# Power_supply_UCM.net
KiCad netlist of a schematic drawn in Altium Designer
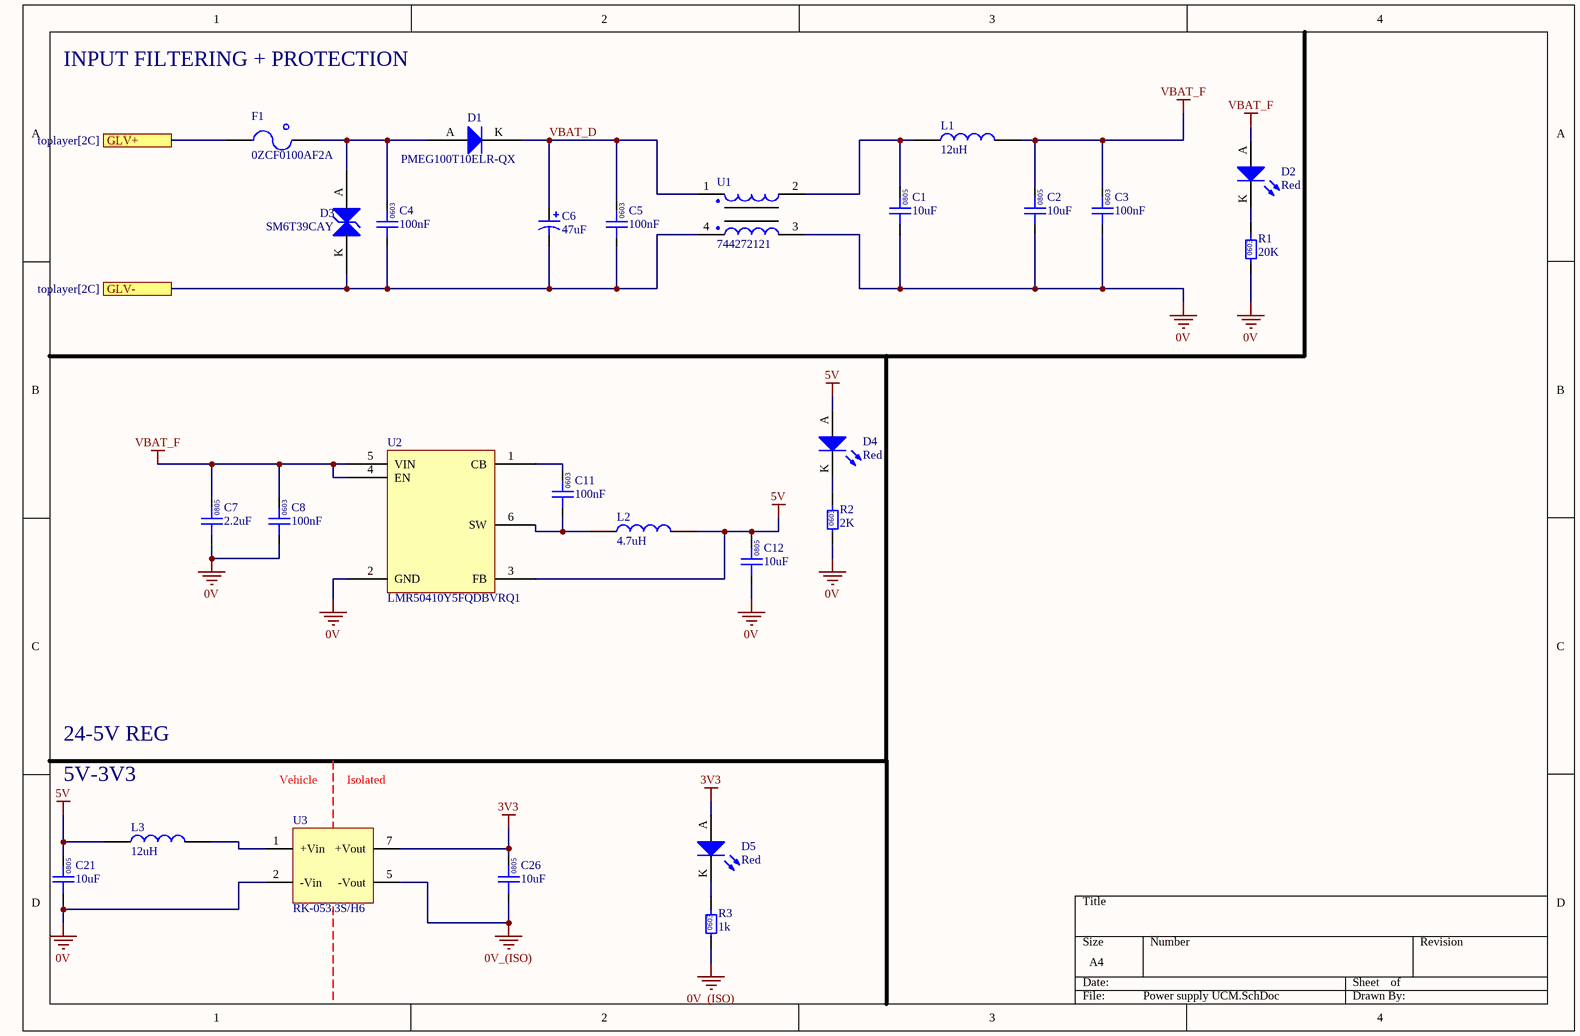
[diagram p0: Power supply UCM.SchDoc]

(export (version "E")
  (design (tool "Eeschema 10.0.6"))
  (components
    (comp (ref "C1")
      (value "10uF")
      (footprint "0805")
      (fields
        (field (name "PART NUMBER") "GRM21BR6YA106KE43L")
        (field (name "MANUFACTURER") "muRata")
        (field (name "TOLERANCE") "10%")
      )
      (libsource (lib "ts_standard_library") (part "Capacitor 0805"))
    )
    (comp (ref "C2")
      (value "10uF")
      (footprint "0805")
      (fields
        (field (name "PART NUMBER") "GRM21BR6YA106KE43L")
        (field (name "MANUFACTURER") "muRata")
        (field (name "TOLERANCE") "10%")
      )
      (libsource (lib "ts_standard_library") (part "Capacitor 0805"))
    )
    (comp (ref "C3")
      (value "100nF")
      (footprint "0603")
      (fields
        (field (name "PART NUMBER") "GCM188L81H104KA57D")
        (field (name "MANUFACTURER") "muRata")
        (field (name "TOLERANCE") "±10%")
      )
      (libsource (lib "ts_standard_library") (part "Capacitor 0603"))
    )
    (comp (ref "C4")
      (value "100nF")
      (footprint "0603")
      (fields
        (field (name "PART NUMBER") "GCM188L81H104KA57D")
        (field (name "MANUFACTURER") "muRata")
        (field (name "TOLERANCE") "±10%")
      )
      (libsource (lib "ts_standard_library") (part "Capacitor 0603"))
    )
    (comp (ref "C5")
      (value "100nF")
      (footprint "0603")
      (fields
        (field (name "PART NUMBER") "GCM188L81H104KA57D")
        (field (name "MANUFACTURER") "muRata")
        (field (name "TOLERANCE") "±10%")
      )
      (libsource (lib "ts_standard_library") (part "Capacitor 0603"))
    )
    (comp (ref "C6")
      (value "47uF")
      (footprint "CHEMI-CON ELCO")
      (fields (field (name "PART NUMBER") "HHXA350ARA470MF61G"))
      (libsource (lib "ts_standard_library") (part "Capacitor (Polarised)"))
    )
    (comp (ref "C7")
      (value "2.2uF")
      (footprint "0805")
      (fields
        (field (name "PART NUMBER") "GRM21BR61A226ME51L")
        (field (name "MANUFACTURER") "muRata")
        (field (name "TOLERANCE") "20%")
      )
      (libsource (lib "ts_standard_library") (part "Capacitor 0805"))
    )
    (comp (ref "C8")
      (value "100nF")
      (footprint "0603")
      (fields
        (field (name "PART NUMBER") "GCM188L81H104KA57D")
        (field (name "MANUFACTURER") "muRata")
        (field (name "TOLERANCE") "±10%")
      )
      (libsource (lib "ts_standard_library") (part "Capacitor 0603"))
    )
    (comp (ref "C11")
      (value "100nF")
      (footprint "0603")
      (fields
        (field (name "PART NUMBER") "GCM188L81H104KA57D")
        (field (name "MANUFACTURER") "muRata")
        (field (name "TOLERANCE") "±10%")
      )
      (libsource (lib "ts_standard_library") (part "Capacitor 0603"))
    )
    (comp (ref "C12")
      (value "10uF")
      (footprint "0805")
      (fields
        (field (name "PART NUMBER") "GRM21BR6YA106KE43L")
        (field (name "MANUFACTURER") "muRata")
        (field (name "TOLERANCE") "10%")
      )
      (libsource (lib "ts_standard_library") (part "Capacitor 0805"))
    )
    (comp (ref "C21")
      (value "10uF")
      (footprint "0805")
      (fields
        (field (name "PART NUMBER") "GRM21BR6YA106KE43L")
        (field (name "MANUFACTURER") "muRata")
        (field (name "TOLERANCE") "10%")
      )
      (libsource (lib "ts_standard_library") (part "Capacitor 0805"))
    )
    (comp (ref "C26")
      (value "10uF")
      (footprint "0805")
      (fields
        (field (name "PART NUMBER") "GRM21BR6YA106KE43L")
        (field (name "MANUFACTURER") "muRata")
        (field (name "TOLERANCE") "10%")
      )
      (libsource (lib "ts_standard_library") (part "Capacitor 0805"))
    )
    (comp (ref "D1")
      (value "PMEG100T10ELR-QX")
      (footprint "SODFL350X110-2N")
      (description "Diode 100 V 1A Surface Mount SOD-123W")
      (libsource (lib "Team Swinburne") (part "PMEG100T10ELR-QX"))
    )
    (comp (ref "D2")
      (value "Red")
      (footprint "0805 LED")
      (description "Red LED Indication - Discrete 1.75V 0805 (2012 Metric)")
      (fields (field (name "PART NUMBER") "SML-210LTT86") (field (name "MANUFACTURER") "ROHM Semiconductor"))
      (libsource (lib "ts_standard_library") (part "LED"))
    )
    (comp (ref "D3")
      (value "SM6T39CAY")
      (footprint "SM6T39CAY-Footprint-1")
      (description "TVS Diode Single Bi-Dir 33.3V 600W Automotive 2-Pin SMB T/R / TVS DIODE 33.3VWM 69.7VC SMB")
      (libsource (lib "Team Swinburne") (part "SM6T39CAY-Symbol"))
    )
    (comp (ref "D4")
      (value "Red")
      (footprint "0805 LED")
      (description "Red LED Indication - Discrete 1.75V 0805 (2012 Metric)")
      (fields (field (name "PART NUMBER") "SML-210LTT86") (field (name "MANUFACTURER") "ROHM Semiconductor"))
      (libsource (lib "ts_standard_library") (part "LED"))
    )
    (comp (ref "D5")
      (value "Red")
      (footprint "0805 LED")
      (description "Red LED Indication - Discrete 1.75V 0805 (2012 Metric)")
      (fields (field (name "PART NUMBER") "SML-210LTT86") (field (name "MANUFACTURER") "ROHM Semiconductor"))
      (libsource (lib "ts_standard_library") (part "LED"))
    )
    (comp (ref "F1")
      (value "0ZCF0100AF2A")
      (footprint "2920")
      (description "PTC RESET FUSE 60V 1A 292")
      (fields
        (field (name "MANUFACTURER") "Littelfuse Inc.")
        (field (name "DIGIKEY PART NUMBER") "507-2070-1-ND")
      )
      (libsource (lib "ts_standard_library") (part "PTC Fuse"))
    )
    (comp (ref "L1")
      (value "12uH")
      (footprint "1812")
      (fields
        (field (name "PART NUMBER") "RLS-126")
        (field (name "MANUFACTURER") "Recom")
        (field (name "TOLERANCE") "0.2")
      )
      (libsource (lib "ts_standard_library") (part "Inductor"))
    )
    (comp (ref "L2")
      (value "4.7uH")
      (footprint "SRN3015TA-4R7M")
      (fields
        (field (name "PART NUMBER") "SRN4018-4R7M")
        (field (name "MANUFACTURER") "Bourns")
        (field (name "TOLERANCE") "0.2")
      )
      (libsource (lib "ts_standard_library") (part "Inductor"))
    )
    (comp (ref "L3")
      (value "12uH")
      (footprint "1812")
      (fields
        (field (name "PART NUMBER") "RLS-126")
        (field (name "MANUFACTURER") "Recom")
        (field (name "TOLERANCE") "0.2")
      )
      (libsource (lib "ts_standard_library") (part "Inductor"))
    )
    (comp (ref "R1")
      (value "20K")
      (footprint "0603")
      (fields
        (field (name "PART NUMBER") "RC0603FR-0720KL")
        (field (name "MANUFACTURER") "YAGEO")
        (field (name "TOLERANCE") "0.01")
      )
      (libsource (lib "ts_standard_library") (part "Resistor 0603"))
    )
    (comp (ref "R2")
      (value "2K")
      (footprint "0603")
      (fields
        (field (name "PART NUMBER") "RC0603FR-072KL")
        (field (name "MANUFACTURER") "YAGEO")
        (field (name "TOLERANCE") "0.01")
      )
      (libsource (lib "ts_standard_library") (part "Resistor 0603"))
    )
    (comp (ref "R3")
      (value "1k")
      (footprint "0603")
      (fields
        (field (name "PART NUMBER") "RC0603FR-071KL")
        (field (name "MANUFACTURER") "YAGEO")
        (field (name "TOLERANCE") "0.01")
      )
      (libsource (lib "ts_standard_library") (part "Resistor 0603"))
    )
    (comp (ref "U1")
      (value "744272121")
      (footprint "Wurth 4-PC Pad")
      (fields
        (field (name "MANUFACTURER") "Wurth Electronics Inc")
        (field (name "DIGIKEY PART NUMBER") "732-1489-1-ND")
      )
      (libsource (lib "ts_standard_library") (part "CM Choke"))
    )
    (comp (ref "U2")
      (value "LMR50410Y5FQDBVRQ1")
      (footprint "TI-SOT23-6")
      (description "IC REG BUCK 5V 1A SOT23-6")
      (fields (field (name "PART NUMBER") "LMR50410-Q1") (field (name "MANUFACTURER") "Texas Instruments"))
      (libsource (lib "ts_standard_library") (part "LMR50410Y5FQDBVRQ1"))
    )
    (comp (ref "U3")
      (value "RK-053.3S/H6")
      (footprint "RK-053.3S/H6")
      (description "DC DC CONVERTER 3.3V 1W")
      (fields (field (name "MANUFACTURER") "Recom"))
      (libsource (lib "ts_standard_library") (part "RK-053.3S/H6"))
    )
  )
  (nets
    (net (code "1") (name "/GLV+") (class "Default")
      (node (ref "F1") (pin "1") (pinfunction "1_1") (pintype "passive"))
    )
    (net (code "2") (name "/GLV-") (class "Default")
      (node (ref "C4") (pin "1") (pinfunction "1_1") (pintype "passive"))
      (node (ref "C5") (pin "1") (pinfunction "1_1") (pintype "passive"))
      (node (ref "C6") (pin "1") (pinfunction "1_1") (pintype "passive"))
      (node (ref "D3") (pin "K") (pintype "passive"))
      (node (ref "U1") (pin "4") (pinfunction "4_4") (pintype "passive"))
    )
    (net (code "3") (name "/VBAT_D") (class "Default")
      (node (ref "C5") (pin "2") (pinfunction "2_2") (pintype "passive"))
      (node (ref "C6") (pin "2") (pinfunction "2_2") (pintype "passive"))
      (node (ref "D1") (pin "K") (pintype "passive"))
      (node (ref "U1") (pin "1") (pinfunction "1_1") (pintype "passive"))
    )
    (net (code "4") (name "0V") (class "Default")
      (node (ref "C1") (pin "1") (pinfunction "1_1") (pintype "passive"))
      (node (ref "C12") (pin "1") (pinfunction "1_1") (pintype "passive"))
      (node (ref "C2") (pin "1") (pinfunction "1_1") (pintype "passive"))
      (node (ref "C21") (pin "1") (pinfunction "1_1") (pintype "passive"))
      (node (ref "C3") (pin "1") (pinfunction "1_1") (pintype "passive"))
      (node (ref "C7") (pin "1") (pinfunction "1_1") (pintype "passive"))
      (node (ref "C8") (pin "1") (pinfunction "1_1") (pintype "passive"))
      (node (ref "R1") (pin "1") (pinfunction "1_1") (pintype "passive"))
      (node (ref "R2") (pin "1") (pinfunction "1_1") (pintype "passive"))
      (node (ref "U1") (pin "3") (pinfunction "3_3") (pintype "power_in"))
      (node (ref "U2") (pin "2") (pinfunction "GND_2") (pintype "passive"))
      (node (ref "U3") (pin "2") (pinfunction "-Vin_2") (pintype "power_in"))
    )
    (net (code "5") (name "0V_(ISO)") (class "Default")
      (node (ref "C26") (pin "1") (pinfunction "1_1") (pintype "passive"))
      (node (ref "R3") (pin "1") (pinfunction "1_1") (pintype "passive"))
      (node (ref "U3") (pin "5") (pinfunction "-Vout_5") (pintype "power_in"))
    )
    (net (code "6") (name "3V3") (class "Default")
      (node (ref "C26") (pin "2") (pinfunction "2_2") (pintype "passive"))
      (node (ref "D5") (pin "A") (pinfunction "A_A") (pintype "passive"))
      (node (ref "U3") (pin "7") (pinfunction "+Vout_7") (pintype "power_in"))
    )
    (net (code "7") (name "5V") (class "Default")
      (node (ref "C12") (pin "2") (pinfunction "2_2") (pintype "passive"))
      (node (ref "C21") (pin "2") (pinfunction "2_2") (pintype "passive"))
      (node (ref "D4") (pin "A") (pinfunction "A_A") (pintype "passive"))
      (node (ref "L2") (pin "1") (pinfunction "1_1") (pintype "passive"))
      (node (ref "L3") (pin "2") (pinfunction "2_2") (pintype "passive"))
      (node (ref "U2") (pin "3") (pinfunction "FB_3") (pintype "passive"))
    )
    (net (code "8") (name "Net-(C1-Pad2)") (class "Default")
      (node (ref "C1") (pin "2") (pinfunction "2_2") (pintype "passive"))
      (node (ref "L1") (pin "2") (pinfunction "2_2") (pintype "passive"))
      (node (ref "U1") (pin "2") (pinfunction "2_2") (pintype "passive"))
    )
    (net (code "9") (name "Net-(C4-Pad2)") (class "Default")
      (node (ref "C4") (pin "2") (pinfunction "2_2") (pintype "passive"))
      (node (ref "D1") (pin "A") (pintype "passive"))
      (node (ref "D3") (pin "A") (pintype "passive"))
      (node (ref "F1") (pin "2") (pinfunction "2_2") (pintype "passive"))
    )
    (net (code "10") (name "Net-(D2-PadK)") (class "Default")
      (node (ref "D2") (pin "K") (pinfunction "K_K") (pintype "passive"))
      (node (ref "R1") (pin "2") (pinfunction "2_2") (pintype "passive"))
    )
    (net (code "11") (name "Net-(D4-PadK)") (class "Default")
      (node (ref "D4") (pin "K") (pinfunction "K_K") (pintype "passive"))
      (node (ref "R2") (pin "2") (pinfunction "2_2") (pintype "passive"))
    )
    (net (code "12") (name "Net-(D5-PadK)") (class "Default")
      (node (ref "D5") (pin "K") (pinfunction "K_K") (pintype "passive"))
      (node (ref "R3") (pin "2") (pinfunction "2_2") (pintype "passive"))
    )
    (net (code "13") (name "Net-(U2-CB)") (class "Default")
      (node (ref "C11") (pin "2") (pinfunction "2_2") (pintype "passive"))
      (node (ref "U2") (pin "1") (pinfunction "CB_1") (pintype "passive"))
    )
    (net (code "14") (name "Net-(U2-SW)") (class "Default")
      (node (ref "C11") (pin "1") (pinfunction "1_1") (pintype "passive"))
      (node (ref "L2") (pin "2") (pinfunction "2_2") (pintype "passive"))
      (node (ref "U2") (pin "6") (pinfunction "SW_6") (pintype "passive"))
    )
    (net (code "15") (name "Net-(U3-+Vin)") (class "Default")
      (node (ref "L3") (pin "1") (pinfunction "1_1") (pintype "passive"))
      (node (ref "U3") (pin "1") (pinfunction "+Vin_1") (pintype "power_in"))
    )
    (net (code "16") (name "VBAT_F") (class "Default")
      (node (ref "C2") (pin "2") (pinfunction "2_2") (pintype "passive"))
      (node (ref "C3") (pin "2") (pinfunction "2_2") (pintype "passive"))
      (node (ref "C7") (pin "2") (pinfunction "2_2") (pintype "passive"))
      (node (ref "C8") (pin "2") (pinfunction "2_2") (pintype "passive"))
      (node (ref "D2") (pin "A") (pinfunction "A_A") (pintype "passive"))
      (node (ref "L1") (pin "1") (pinfunction "1_1") (pintype "passive"))
      (node (ref "U2") (pin "4") (pinfunction "EN_4") (pintype "passive"))
      (node (ref "U2") (pin "5") (pinfunction "VIN_5") (pintype "passive"))
    )
  )
)
